# 10_-MAIN_POWER.net
KiCad netlist of a schematic drawn in Altium Designer
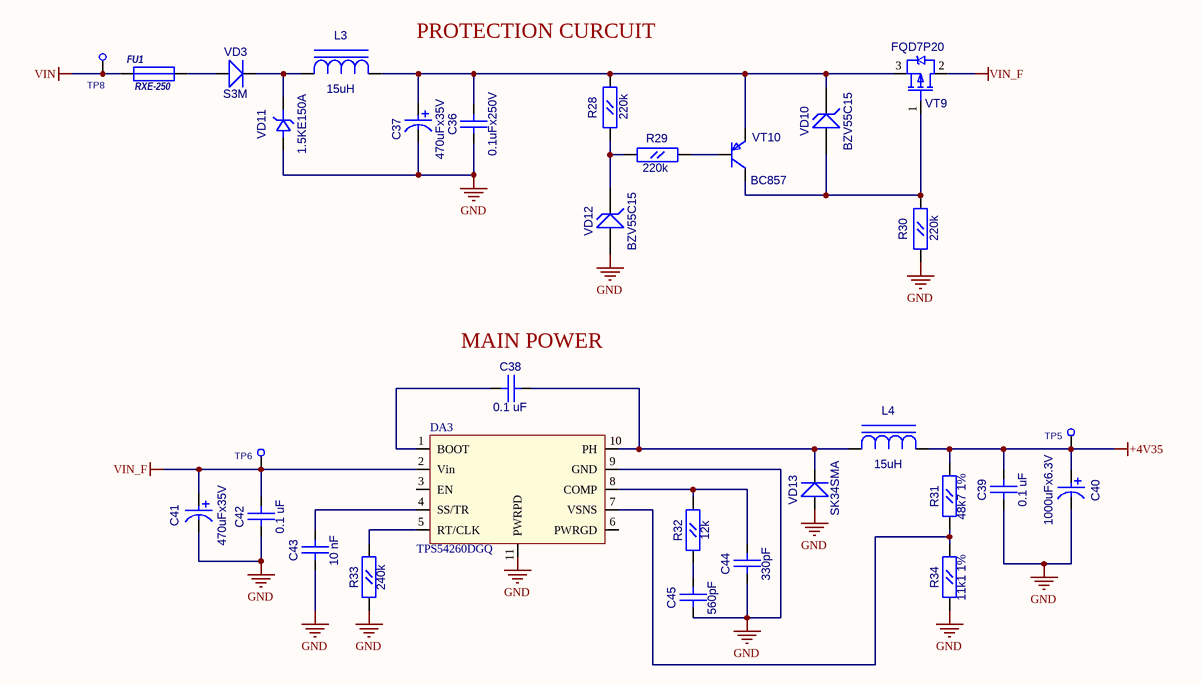
[diagram p0: [10]-MAIN_POWER.SchDoc]

(export (version "E")
  (design (tool "Eeschema 10.0.6"))
  (components
    (comp (ref "C36")
      (value "0.1uFx250V")
      (footprint "CC1206")
      (description "CC1206")
      (libsource (lib "gprs_modem_2") (part "CC1206"))
    )
    (comp (ref "C37")
      (value "470uFx35V")
      (footprint "CC16X10_CAP0.5(1)(Primary)")
      (description "CAP0.5(1)")
      (libsource (lib "gprs_modem_2") (part "CAP0.5(1)"))
    )
    (comp (ref "C38")
      (value "0.1 uF")
      (footprint "CC0603")
      (description "CC0603")
      (libsource (lib "gprs_modem_2") (part "CC0603"))
    )
    (comp (ref "C39")
      (value "0.1 uF")
      (footprint "CC0603")
      (description "CC0603")
      (libsource (lib "gprs_modem_2") (part "CC0603"))
    )
    (comp (ref "C40")
      (value "1000uFx6.3V")
      (footprint "CC8X3.5")
      (description "CAP0.35")
      (libsource (lib "gprs_modem_2") (part "CAP0.35"))
    )
    (comp (ref "C41")
      (value "470uFx35V")
      (footprint "CC16X10_CAP0.5(1)(Primary)")
      (description "CAP0.5(1)")
      (libsource (lib "gprs_modem_2") (part "CAP0.5(1)"))
    )
    (comp (ref "C42")
      (value "0.1 uF")
      (footprint "CC0603")
      (description "CC0603")
      (libsource (lib "gprs_modem_2") (part "CC0603"))
    )
    (comp (ref "C43")
      (value "10 nF")
      (footprint "CC0603")
      (description "CC0603")
      (libsource (lib "gprs_modem_2") (part "CC0603"))
    )
    (comp (ref "C44")
      (value "330pF")
      (footprint "CC0603")
      (description "CC0603")
      (libsource (lib "gprs_modem_2") (part "CC0603"))
    )
    (comp (ref "C45")
      (value "560pF")
      (footprint "CC0603")
      (description "CC0603")
      (libsource (lib "gprs_modem_2") (part "CC0603"))
    )
    (comp (ref "DA3")
      (value "TPS54260DGQ")
      (footprint "S-PDSO-G10")
      (libsource (lib "gprs_modem_2") (part "TPS54260DGQ"))
    )
    (comp (ref "FU1")
      (value "RXE-250")
      (footprint "RXE-185")
      (description "RXE-185")
      (libsource (lib "fizik_lib") (part "RXE-185"))
    )
    (comp (ref "L3")
      (value "15uH")
      (footprint "SDR0805")
      (description "SDR0805")
      (libsource (lib "gprs_modem_2") (part "SDR0805"))
    )
    (comp (ref "L4")
      (value "15uH")
      (footprint "SDR0805")
      (description "SDR0805")
      (libsource (lib "gprs_modem_2") (part "SDR0805"))
    )
    (comp (ref "R28")
      (value "220k")
      (footprint "RC0603")
      (description "RC0603")
      (libsource (lib "gprs_modem_2") (part "RC0603"))
    )
    (comp (ref "R29")
      (value "220k")
      (footprint "RC0603")
      (description "RC0603")
      (libsource (lib "gprs_modem_2") (part "RC0603"))
    )
    (comp (ref "R30")
      (value "220k")
      (footprint "RC0603")
      (description "RC0603")
      (libsource (lib "gprs_modem_2") (part "RC0603"))
    )
    (comp (ref "R31")
      (value "48k7 1%")
      (footprint "RC0603")
      (description "RC0603")
      (libsource (lib "gprs_modem_2") (part "RC0603"))
    )
    (comp (ref "R32")
      (value "12k")
      (footprint "RC0603")
      (description "RC0603")
      (libsource (lib "gprs_modem_2") (part "RC0603"))
    )
    (comp (ref "R33")
      (value "240k")
      (footprint "RC0603")
      (description "RC0603")
      (libsource (lib "gprs_modem_2") (part "RC0603"))
    )
    (comp (ref "R34")
      (value "11k1 1%")
      (footprint "RC0603")
      (description "RC0603")
      (libsource (lib "gprs_modem_2") (part "RC0603"))
    )
    (comp (ref "TP5")
      (value "TESTPOINT1")
      (footprint "TESTPOINT1")
      (libsource (lib "fizik_lib") (part "TESTPOINT1"))
    )
    (comp (ref "TP6")
      (value "TESTPOINT1")
      (footprint "TESTPOINT1")
      (libsource (lib "fizik_lib") (part "TESTPOINT1"))
    )
    (comp (ref "TP8")
      (value "TESTPOINT1")
      (footprint "TESTPOINT1")
      (libsource (lib "fizik_lib") (part "TESTPOINT1"))
    )
    (comp (ref "VD3")
      (value "S3M")
      (footprint "SMC")
      (description "Schottky Rectifier")
      (libsource (lib "fizik_lib") (part "S3A"))
    )
    (comp (ref "VD10")
      (value "BZV55C15")
      (footprint "SOD-80")
      (description "Zener Voltage Regulator Diode")
      (libsource (lib "gprs_modem_2") (part "BZV55C12"))
    )
    (comp (ref "VD11")
      (value "1.5KE150A")
      (footprint "DO-201")
      (description "1.5KE")
      (libsource (lib "gprs_modem") (part "1.5KE"))
    )
    (comp (ref "VD12")
      (value "BZV55C15")
      (footprint "SOD-80")
      (description "Zener Voltage Regulator Diode")
      (libsource (lib "gprs_modem_2") (part "BZV55C12"))
    )
    (comp (ref "VD13")
      (value "SK34SMA")
      (footprint "SMA")
      (description "Schottky Rectifier")
      (libsource (lib "gprs_modem") (part "SK34SMA"))
    )
    (comp (ref "VT9")
      (value "FQD7P20")
      (footprint "D-PAK(TO-252AA)")
      (description "HEXFET Power MOSFET")
      (libsource (lib "gprs_modem_2") (part "IRFR9220"))
    )
    (comp (ref "VT10")
      (value "BC857")
      (footprint "SOT-23(123)")
      (description "PNP 100ma transistor")
      (libsource (lib "gprs_modem_2") (part "BC857B"))
    )
  )
  (nets
    (net (code "1") (name "+4V35") (class "Default")
      (node (ref "C39") (pin "1") (pinfunction "A_1") (pintype "passive"))
      (node (ref "C40") (pin "1") (pintype "passive"))
      (node (ref "L4") (pin "2") (pinfunction "A_2") (pintype "passive"))
      (node (ref "R31") (pin "2") (pinfunction "B_2") (pintype "passive"))
      (node (ref "TP5") (pin "1") (pintype "passive"))
    )
    (net (code "2") (name "GND") (class "Default")
      (node (ref "C36") (pin "1") (pinfunction "A_1") (pintype "passive"))
      (node (ref "C37") (pin "1") (pintype "passive"))
      (node (ref "C39") (pin "2") (pinfunction "B_2") (pintype "passive"))
      (node (ref "C40") (pin "2") (pintype "passive"))
      (node (ref "C41") (pin "1") (pintype "passive"))
      (node (ref "C42") (pin "2") (pinfunction "B_2") (pintype "passive"))
      (node (ref "C43") (pin "2") (pinfunction "B_2") (pintype "passive"))
      (node (ref "C44") (pin "2") (pinfunction "B_2") (pintype "passive"))
      (node (ref "C45") (pin "2") (pinfunction "B_2") (pintype "passive"))
      (node (ref "DA3") (pin "11") (pinfunction "PWRPD_11") (pintype "passive"))
      (node (ref "DA3") (pin "9") (pinfunction "GND_9") (pintype "passive"))
      (node (ref "R30") (pin "1") (pinfunction "A_1") (pintype "passive"))
      (node (ref "R33") (pin "1") (pinfunction "A_1") (pintype "passive"))
      (node (ref "R34") (pin "1") (pinfunction "A_1") (pintype "passive"))
      (node (ref "VD11") (pin "1") (pinfunction "A_1") (pintype "passive"))
      (node (ref "VD12") (pin "1") (pinfunction "A_1") (pintype "passive"))
      (node (ref "VD13") (pin "1") (pinfunction "A_1") (pintype "passive"))
    )
    (net (code "3") (name "Net-(C36-B)") (class "Default")
      (node (ref "C36") (pin "2") (pinfunction "B_2") (pintype "passive"))
      (node (ref "C37") (pin "2") (pintype "passive"))
      (node (ref "L3") (pin "2") (pinfunction "A_2") (pintype "passive"))
      (node (ref "R28") (pin "2") (pinfunction "B_2") (pintype "passive"))
      (node (ref "VD10") (pin "2") (pintype "passive"))
      (node (ref "VT10") (pin "2") (pinfunction "E_2") (pintype "passive"))
      (node (ref "VT9") (pin "3") (pinfunction "S_3") (pintype "passive"))
    )
    (net (code "4") (name "Net-(C38-A)") (class "Default")
      (node (ref "C38") (pin "1") (pinfunction "A_1") (pintype "passive"))
      (node (ref "DA3") (pin "10") (pinfunction "PH_10") (pintype "passive"))
      (node (ref "L4") (pin "1") (pinfunction "C_1") (pintype "passive"))
      (node (ref "VD13") (pin "2") (pinfunction "K_2") (pintype "passive"))
    )
    (net (code "5") (name "Net-(C38-B)") (class "Default")
      (node (ref "C38") (pin "2") (pinfunction "B_2") (pintype "passive"))
      (node (ref "DA3") (pin "1") (pinfunction "BOOT_1") (pintype "passive"))
    )
    (net (code "6") (name "Net-(C43-A)") (class "Default")
      (node (ref "C43") (pin "1") (pinfunction "A_1") (pintype "passive"))
      (node (ref "DA3") (pin "4") (pinfunction "SS/TR_4") (pintype "passive"))
    )
    (net (code "7") (name "Net-(C44-A)") (class "Default")
      (node (ref "C44") (pin "1") (pinfunction "A_1") (pintype "passive"))
      (node (ref "DA3") (pin "8") (pinfunction "COMP_8") (pintype "passive"))
      (node (ref "R32") (pin "2") (pinfunction "B_2") (pintype "passive"))
    )
    (net (code "8") (name "Net-(C45-A)") (class "Default")
      (node (ref "C45") (pin "1") (pinfunction "A_1") (pintype "passive"))
      (node (ref "R32") (pin "1") (pinfunction "A_1") (pintype "passive"))
    )
    (net (code "9") (name "Net-(DA3-RT{slash}CLK)") (class "Default")
      (node (ref "DA3") (pin "5") (pinfunction "RT/CLK_5") (pintype "passive"))
      (node (ref "R33") (pin "2") (pinfunction "B_2") (pintype "passive"))
    )
    (net (code "10") (name "Net-(DA3-VSNS)") (class "Default")
      (node (ref "DA3") (pin "7") (pinfunction "VSNS_7") (pintype "passive"))
      (node (ref "R31") (pin "1") (pinfunction "A_1") (pintype "passive"))
      (node (ref "R34") (pin "2") (pinfunction "B_2") (pintype "passive"))
    )
    (net (code "11") (name "Net-(L3-C)") (class "Default")
      (node (ref "L3") (pin "1") (pinfunction "C_1") (pintype "passive"))
      (node (ref "VD11") (pin "2") (pinfunction "K_2") (pintype "passive"))
      (node (ref "VD3") (pin "2") (pinfunction "K_2") (pintype "passive"))
    )
    (net (code "12") (name "Net-(R28-A)") (class "Default")
      (node (ref "R28") (pin "1") (pinfunction "A_1") (pintype "passive"))
      (node (ref "R29") (pin "2") (pinfunction "B_2") (pintype "passive"))
      (node (ref "VD12") (pin "2") (pintype "passive"))
    )
    (net (code "13") (name "Net-(R29-A)") (class "Default")
      (node (ref "R29") (pin "1") (pinfunction "A_1") (pintype "passive"))
      (node (ref "VT10") (pin "1") (pinfunction "B_1") (pintype "passive"))
    )
    (net (code "14") (name "Net-(R30-B)") (class "Default")
      (node (ref "R30") (pin "2") (pinfunction "B_2") (pintype "passive"))
      (node (ref "VD10") (pin "1") (pinfunction "A_1") (pintype "passive"))
      (node (ref "VT10") (pin "3") (pinfunction "C_3") (pintype "passive"))
      (node (ref "VT9") (pin "1") (pinfunction "G_1") (pintype "passive"))
    )
    (net (code "15") (name "Net-(VD3-A)") (class "Default")
      (node (ref "FU1") (pin "2") (pintype "passive"))
      (node (ref "VD3") (pin "1") (pinfunction "A_1") (pintype "passive"))
    )
    (net (code "16") (name "VIN") (class "Default")
      (node (ref "FU1") (pin "1") (pintype "passive"))
      (node (ref "TP8") (pin "1") (pintype "passive"))
    )
    (net (code "17") (name "VIN_F") (class "Default")
      (node (ref "C41") (pin "2") (pintype "passive"))
      (node (ref "C42") (pin "1") (pinfunction "A_1") (pintype "passive"))
      (node (ref "DA3") (pin "2") (pinfunction "Vin_2") (pintype "passive"))
      (node (ref "TP6") (pin "1") (pintype "passive"))
      (node (ref "VT9") (pin "2") (pinfunction "D_2") (pintype "passive"))
    )
    (net (code "18") (name "unconnected-(DA3-EN-Pad3)") (class "Default")
      (node (ref "DA3") (pin "3") (pinfunction "EN_3") (pintype "passive"))
    )
    (net (code "19") (name "unconnected-(DA3-PWRGD-Pad6)") (class "Default")
      (node (ref "DA3") (pin "6") (pinfunction "PWRGD_6") (pintype "passive"))
    )
  )
)
